# First_PCB_dip.net
KiCad netlist of a schematic drawn in Altium Designer
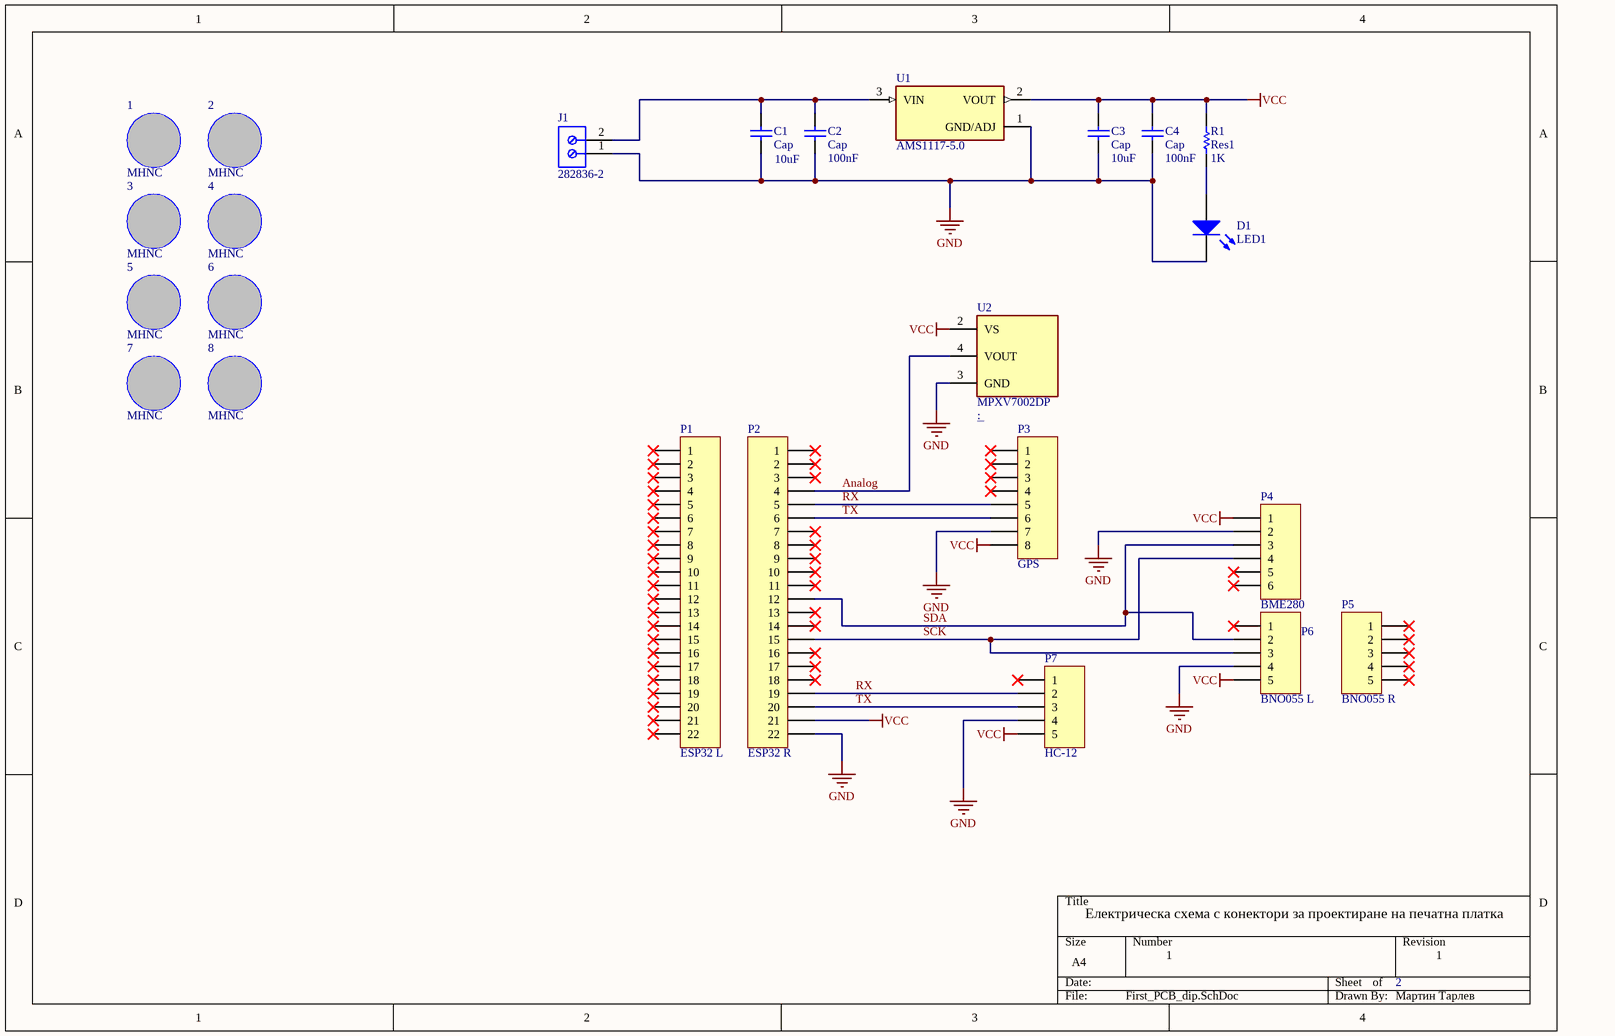
[diagram p0: First_PCB_dip.SchDoc]

(export (version "E")
  (design (tool "Eeschema 10.0.6"))
  (components
    (comp (ref "1") (value "MHNC") (footprint "MHNC") (libsource (lib "First_PCB_dip") (part "MHNC")))
    (comp (ref "2") (value "MHNC") (footprint "MHNC") (libsource (lib "First_PCB_dip") (part "MHNC")))
    (comp (ref "3") (value "MHNC") (footprint "MHNC") (libsource (lib "First_PCB_dip") (part "MHNC")))
    (comp (ref "4") (value "MHNC") (footprint "MHNC") (libsource (lib "First_PCB_dip") (part "MHNC")))
    (comp (ref "5") (value "MHNC") (footprint "MHNC") (libsource (lib "First_PCB_dip") (part "MHNC")))
    (comp (ref "6") (value "MHNC") (footprint "MHNC") (libsource (lib "First_PCB_dip") (part "MHNC")))
    (comp (ref "7") (value "MHNC") (footprint "MHNC") (libsource (lib "First_PCB_dip") (part "MHNC")))
    (comp (ref "8") (value "MHNC") (footprint "MHNC") (libsource (lib "First_PCB_dip") (part "MHNC")))
    (comp (ref "C1")
      (value "Cap")
      (footprint "CAP2")
      (description "Capacitor")
      (fields (field (name "ALTIUM_VALUE") "10uF") (field (name "PUBLISHER") "Altium Limited"))
      (libsource (lib "Miscellaneous Devices") (part "Cap"))
    )
    (comp (ref "C2")
      (value "Cap")
      (footprint "CON")
      (description "Capacitor")
      (fields (field (name "ALTIUM_VALUE") "100nF") (field (name "PUBLISHER") "Altium Limited"))
      (libsource (lib "Miscellaneous Devices") (part "Cap"))
    )
    (comp (ref "C3")
      (value "Cap")
      (footprint "CAP2")
      (description "Capacitor")
      (fields (field (name "ALTIUM_VALUE") "10uF") (field (name "PUBLISHER") "Altium Limited"))
      (libsource (lib "Miscellaneous Devices") (part "Cap"))
    )
    (comp (ref "C4")
      (value "Cap")
      (footprint "CON")
      (description "Capacitor")
      (fields (field (name "ALTIUM_VALUE") "100nF") (field (name "PUBLISHER") "Altium Limited"))
      (libsource (lib "Miscellaneous Devices") (part "Cap"))
    )
    (comp (ref "D1")
      (value "LED1")
      (footprint "LED-1")
      (description "Typical RED GaAs LED")
      (fields (field (name "PUBLISHER") "Altium Limited"))
      (libsource (lib "Miscellaneous Devices") (part "LED1"))
    )
    (comp (ref "J1")
      (value "282836-2")
      (footprint "TECO-282836-2_V")
      (description "Female Header, Pitch 5 mm, 1 x 2 Position, Height 10 mm, Tail Length 3.5 mm, Rohs, Bulk")
      (fields (field (name "VOLTAGE") "300V") (field (name "MANUFACTURER") "TE Connectivity"))
      (libsource (lib "Altium Content Vault") (part "CN-1P-F-TB2"))
    )
    (comp (ref "P1")
      (value "ESP32 L")
      (footprint "HDR1X22")
      (description "Header, 22-Pin")
      (fields (field (name "PUBLISHER") "p"))
      (libsource (lib "") (part "Header 22_1"))
    )
    (comp (ref "P2")
      (value "ESP32 R")
      (footprint "HDR1X22")
      (description "Header, 22-Pin")
      (fields (field (name "PUBLISHER") "Altium Limited"))
      (libsource (lib "Miscellaneous Connectors") (part "Header 22"))
    )
    (comp (ref "P3")
      (value "GPS")
      (footprint "HDR1X8")
      (description "Header, 8-Pin")
      (fields (field (name "PUBLISHER") "Altium Limited"))
      (libsource (lib "Miscellaneous Connectors") (part "Header 8"))
    )
    (comp (ref "P4")
      (value "BME280")
      (footprint "HDR1X6")
      (description "Header, 6-Pin")
      (fields (field (name "PUBLISHER") "Altium Limited"))
      (libsource (lib "Miscellaneous Connectors") (part "Header 6"))
    )
    (comp (ref "P5")
      (value "BNO055 R")
      (footprint "HDR1X5")
      (description "Header, 5-Pin")
      (fields (field (name "PUBLISHER") "Altium Limited"))
      (libsource (lib "") (part "Header 5_1"))
    )
    (comp (ref "P6")
      (value "BNO055 L")
      (footprint "HDR1X5")
      (description "Header, 5-Pin")
      (fields (field (name "PUBLISHER") "Altium Limited"))
      (libsource (lib "Miscellaneous Connectors") (part "Header 5"))
    )
    (comp (ref "P7")
      (value "HC-12")
      (footprint "HDR1X5")
      (description "Header, 5-Pin")
      (fields (field (name "PUBLISHER") "Altium Limited"))
      (libsource (lib "Miscellaneous Connectors") (part "Header 5"))
    )
    (comp (ref "R1")
      (value "Res1")
      (footprint "AXIAL-0.3")
      (description "Resistor")
      (fields (field (name "ALTIUM_VALUE") "1K") (field (name "PUBLISHER") "Altium Limited"))
      (libsource (lib "Miscellaneous Devices") (part "Res1"))
    )
    (comp (ref "U1")
      (value "AMS1117-5.0")
      (footprint "SOT229P700X180-4N")
      (description "1A LOW DROPOUT VOLTAGE REGULATOR")
      (fields (field (name "MF") "ams"))
      (libsource (lib "AMS1117-5.0") (part "AMS1117-5.0"))
    )
    (comp (ref "U2")
      (value "MPXV7002DP")
      (footprint "XDCR_MPXV7002DP")
      (fields (field (name "MF") "NXP USA"))
      (libsource (lib "MPXV7002DP") (part "MPXV7002DP"))
    )
  )
  (nets
    (net (code "1") (name "/Analog") (class "Default")
      (node (ref "P2") (pin "4") (pinfunction "4_4") (pintype "passive"))
      (node (ref "U2") (pin "4") (pinfunction "VOUT_4") (pintype "passive"))
    )
    (net (code "2") (name "/RX") (class "Default")
      (node (ref "P2") (pin "19") (pinfunction "19_19") (pintype "passive"))
      (node (ref "P2") (pin "5") (pinfunction "5_5") (pintype "passive"))
      (node (ref "P3") (pin "5") (pinfunction "5_5") (pintype "passive"))
      (node (ref "P7") (pin "2") (pinfunction "2_2") (pintype "passive"))
    )
    (net (code "3") (name "/SCK") (class "Default")
      (node (ref "P2") (pin "15") (pinfunction "15_15") (pintype "passive"))
      (node (ref "P4") (pin "4") (pinfunction "4_4") (pintype "passive"))
      (node (ref "P6") (pin "3") (pinfunction "3_3") (pintype "passive"))
    )
    (net (code "4") (name "/SDA") (class "Default")
      (node (ref "P2") (pin "12") (pinfunction "12_12") (pintype "passive"))
      (node (ref "P4") (pin "3") (pinfunction "3_3") (pintype "passive"))
      (node (ref "P6") (pin "2") (pinfunction "2_2") (pintype "passive"))
    )
    (net (code "5") (name "/TX") (class "Default")
      (node (ref "P2") (pin "20") (pinfunction "20_20") (pintype "passive"))
      (node (ref "P2") (pin "6") (pinfunction "6_6") (pintype "passive"))
      (node (ref "P3") (pin "6") (pinfunction "6_6") (pintype "passive"))
      (node (ref "P7") (pin "3") (pinfunction "3_3") (pintype "passive"))
    )
    (net (code "6") (name "GND") (class "Default")
      (node (ref "C1") (pin "1") (pinfunction "1_1") (pintype "passive"))
      (node (ref "C2") (pin "1") (pinfunction "1_1") (pintype "passive"))
      (node (ref "C3") (pin "1") (pinfunction "1_1") (pintype "passive"))
      (node (ref "C4") (pin "1") (pinfunction "1_1") (pintype "passive"))
      (node (ref "D1") (pin "2") (pinfunction "K_2") (pintype "passive"))
      (node (ref "J1") (pin "1") (pinfunction "1_1") (pintype "passive"))
      (node (ref "P2") (pin "22") (pinfunction "22_22") (pintype "passive"))
      (node (ref "P3") (pin "7") (pinfunction "7_7") (pintype "passive"))
      (node (ref "P4") (pin "2") (pinfunction "2_2") (pintype "passive"))
      (node (ref "P6") (pin "4") (pinfunction "4_4") (pintype "passive"))
      (node (ref "P7") (pin "4") (pinfunction "4_4") (pintype "passive"))
      (node (ref "U1") (pin "1") (pinfunction "GND/ADJ_1") (pintype "power_in"))
      (node (ref "U2") (pin "3") (pinfunction "GND_3") (pintype "power_in"))
    )
    (net (code "7") (name "Net-(D1-A)") (class "Default")
      (node (ref "D1") (pin "1") (pinfunction "A_1") (pintype "passive"))
      (node (ref "R1") (pin "1") (pinfunction "1_1") (pintype "passive"))
    )
    (net (code "8") (name "Net-(U1-VIN)") (class "Default")
      (node (ref "C1") (pin "2") (pinfunction "2_2") (pintype "passive"))
      (node (ref "C2") (pin "2") (pinfunction "2_2") (pintype "passive"))
      (node (ref "J1") (pin "2") (pinfunction "2_2") (pintype "passive"))
      (node (ref "U1") (pin "3") (pinfunction "VIN_3") (pintype "input"))
    )
    (net (code "9") (name "VCC") (class "Default")
      (node (ref "C3") (pin "2") (pinfunction "2_2") (pintype "passive"))
      (node (ref "C4") (pin "2") (pinfunction "2_2") (pintype "passive"))
      (node (ref "P2") (pin "21") (pinfunction "21_21") (pintype "passive"))
      (node (ref "P3") (pin "8") (pinfunction "8_8") (pintype "passive"))
      (node (ref "P4") (pin "1") (pinfunction "1_1") (pintype "passive"))
      (node (ref "P6") (pin "5") (pinfunction "5_5") (pintype "passive"))
      (node (ref "P7") (pin "5") (pinfunction "5_5") (pintype "passive"))
      (node (ref "R1") (pin "2") (pinfunction "2_2") (pintype "passive"))
      (node (ref "U1") (pin "2") (pinfunction "VOUT_2") (pintype "output"))
      (node (ref "U2") (pin "2") (pinfunction "VS_2") (pintype "passive"))
    )
    (net (code "10") (name "unconnected-(P1-Pad1)") (class "Default")
      (node (ref "P1") (pin "1") (pinfunction "1_1") (pintype "passive+no_connect"))
    )
    (net (code "11") (name "unconnected-(P1-Pad2)") (class "Default")
      (node (ref "P1") (pin "2") (pinfunction "2_2") (pintype "passive+no_connect"))
    )
    (net (code "12") (name "unconnected-(P1-Pad3)") (class "Default")
      (node (ref "P1") (pin "3") (pinfunction "3_3") (pintype "passive+no_connect"))
    )
    (net (code "13") (name "unconnected-(P1-Pad4)") (class "Default")
      (node (ref "P1") (pin "4") (pinfunction "4_4") (pintype "passive+no_connect"))
    )
    (net (code "14") (name "unconnected-(P1-Pad5)") (class "Default")
      (node (ref "P1") (pin "5") (pinfunction "5_5") (pintype "passive+no_connect"))
    )
    (net (code "15") (name "unconnected-(P1-Pad6)") (class "Default")
      (node (ref "P1") (pin "6") (pinfunction "6_6") (pintype "passive+no_connect"))
    )
    (net (code "16") (name "unconnected-(P1-Pad7)") (class "Default")
      (node (ref "P1") (pin "7") (pinfunction "7_7") (pintype "passive+no_connect"))
    )
    (net (code "17") (name "unconnected-(P1-Pad8)") (class "Default")
      (node (ref "P1") (pin "8") (pinfunction "8_8") (pintype "passive+no_connect"))
    )
    (net (code "18") (name "unconnected-(P1-Pad9)") (class "Default")
      (node (ref "P1") (pin "9") (pinfunction "9_9") (pintype "passive+no_connect"))
    )
    (net (code "19") (name "unconnected-(P1-Pad10)") (class "Default")
      (node (ref "P1") (pin "10") (pinfunction "10_10") (pintype "passive+no_connect"))
    )
    (net (code "20") (name "unconnected-(P1-Pad11)") (class "Default")
      (node (ref "P1") (pin "11") (pinfunction "11_11") (pintype "passive+no_connect"))
    )
    (net (code "21") (name "unconnected-(P1-Pad12)") (class "Default")
      (node (ref "P1") (pin "12") (pinfunction "12_12") (pintype "passive+no_connect"))
    )
    (net (code "22") (name "unconnected-(P1-Pad13)") (class "Default")
      (node (ref "P1") (pin "13") (pinfunction "13_13") (pintype "passive+no_connect"))
    )
    (net (code "23") (name "unconnected-(P1-Pad14)") (class "Default")
      (node (ref "P1") (pin "14") (pinfunction "14_14") (pintype "passive+no_connect"))
    )
    (net (code "24") (name "unconnected-(P1-Pad15)") (class "Default")
      (node (ref "P1") (pin "15") (pinfunction "15_15") (pintype "passive+no_connect"))
    )
    (net (code "25") (name "unconnected-(P1-Pad16)") (class "Default")
      (node (ref "P1") (pin "16") (pinfunction "16_16") (pintype "passive+no_connect"))
    )
    (net (code "26") (name "unconnected-(P1-Pad17)") (class "Default")
      (node (ref "P1") (pin "17") (pinfunction "17_17") (pintype "passive+no_connect"))
    )
    (net (code "27") (name "unconnected-(P1-Pad18)") (class "Default")
      (node (ref "P1") (pin "18") (pinfunction "18_18") (pintype "passive+no_connect"))
    )
    (net (code "28") (name "unconnected-(P1-Pad19)") (class "Default")
      (node (ref "P1") (pin "19") (pinfunction "19_19") (pintype "passive+no_connect"))
    )
    (net (code "29") (name "unconnected-(P1-Pad20)") (class "Default")
      (node (ref "P1") (pin "20") (pinfunction "20_20") (pintype "passive+no_connect"))
    )
    (net (code "30") (name "unconnected-(P1-Pad21)") (class "Default")
      (node (ref "P1") (pin "21") (pinfunction "21_21") (pintype "passive+no_connect"))
    )
    (net (code "31") (name "unconnected-(P1-Pad22)") (class "Default")
      (node (ref "P1") (pin "22") (pinfunction "22_22") (pintype "passive+no_connect"))
    )
    (net (code "32") (name "unconnected-(P2-Pad1)") (class "Default")
      (node (ref "P2") (pin "1") (pinfunction "1_1") (pintype "passive+no_connect"))
    )
    (net (code "33") (name "unconnected-(P2-Pad2)") (class "Default")
      (node (ref "P2") (pin "2") (pinfunction "2_2") (pintype "passive+no_connect"))
    )
    (net (code "34") (name "unconnected-(P2-Pad3)") (class "Default")
      (node (ref "P2") (pin "3") (pinfunction "3_3") (pintype "passive+no_connect"))
    )
    (net (code "35") (name "unconnected-(P2-Pad7)") (class "Default")
      (node (ref "P2") (pin "7") (pinfunction "7_7") (pintype "passive+no_connect"))
    )
    (net (code "36") (name "unconnected-(P2-Pad8)") (class "Default")
      (node (ref "P2") (pin "8") (pinfunction "8_8") (pintype "passive+no_connect"))
    )
    (net (code "37") (name "unconnected-(P2-Pad9)") (class "Default")
      (node (ref "P2") (pin "9") (pinfunction "9_9") (pintype "passive+no_connect"))
    )
    (net (code "38") (name "unconnected-(P2-Pad10)") (class "Default")
      (node (ref "P2") (pin "10") (pinfunction "10_10") (pintype "passive+no_connect"))
    )
    (net (code "39") (name "unconnected-(P2-Pad11)") (class "Default")
      (node (ref "P2") (pin "11") (pinfunction "11_11") (pintype "passive+no_connect"))
    )
    (net (code "40") (name "unconnected-(P2-Pad13)") (class "Default")
      (node (ref "P2") (pin "13") (pinfunction "13_13") (pintype "passive+no_connect"))
    )
    (net (code "41") (name "unconnected-(P2-Pad14)") (class "Default")
      (node (ref "P2") (pin "14") (pinfunction "14_14") (pintype "passive+no_connect"))
    )
    (net (code "42") (name "unconnected-(P2-Pad16)") (class "Default")
      (node (ref "P2") (pin "16") (pinfunction "16_16") (pintype "passive+no_connect"))
    )
    (net (code "43") (name "unconnected-(P2-Pad17)") (class "Default")
      (node (ref "P2") (pin "17") (pinfunction "17_17") (pintype "passive+no_connect"))
    )
    (net (code "44") (name "unconnected-(P2-Pad18)") (class "Default")
      (node (ref "P2") (pin "18") (pinfunction "18_18") (pintype "passive+no_connect"))
    )
    (net (code "45") (name "unconnected-(P3-Pad1)") (class "Default")
      (node (ref "P3") (pin "1") (pinfunction "1_1") (pintype "passive+no_connect"))
    )
    (net (code "46") (name "unconnected-(P3-Pad2)") (class "Default")
      (node (ref "P3") (pin "2") (pinfunction "2_2") (pintype "passive+no_connect"))
    )
    (net (code "47") (name "unconnected-(P3-Pad3)") (class "Default")
      (node (ref "P3") (pin "3") (pinfunction "3_3") (pintype "passive+no_connect"))
    )
    (net (code "48") (name "unconnected-(P3-Pad4)") (class "Default")
      (node (ref "P3") (pin "4") (pinfunction "4_4") (pintype "passive+no_connect"))
    )
    (net (code "49") (name "unconnected-(P4-Pad5)") (class "Default")
      (node (ref "P4") (pin "5") (pinfunction "5_5") (pintype "passive+no_connect"))
    )
    (net (code "50") (name "unconnected-(P4-Pad6)") (class "Default")
      (node (ref "P4") (pin "6") (pinfunction "6_6") (pintype "passive+no_connect"))
    )
    (net (code "51") (name "unconnected-(P5-Pad1)") (class "Default")
      (node (ref "P5") (pin "1") (pinfunction "1_1") (pintype "passive+no_connect"))
    )
    (net (code "52") (name "unconnected-(P5-Pad2)") (class "Default")
      (node (ref "P5") (pin "2") (pinfunction "2_2") (pintype "passive+no_connect"))
    )
    (net (code "53") (name "unconnected-(P5-Pad3)") (class "Default")
      (node (ref "P5") (pin "3") (pinfunction "3_3") (pintype "passive+no_connect"))
    )
    (net (code "54") (name "unconnected-(P5-Pad4)") (class "Default")
      (node (ref "P5") (pin "4") (pinfunction "4_4") (pintype "passive+no_connect"))
    )
    (net (code "55") (name "unconnected-(P5-Pad5)") (class "Default")
      (node (ref "P5") (pin "5") (pinfunction "5_5") (pintype "passive+no_connect"))
    )
    (net (code "56") (name "unconnected-(P6-Pad1)") (class "Default")
      (node (ref "P6") (pin "1") (pinfunction "1_1") (pintype "passive+no_connect"))
    )
    (net (code "57") (name "unconnected-(P7-Pad1)") (class "Default")
      (node (ref "P7") (pin "1") (pinfunction "1_1") (pintype "passive+no_connect"))
    )
  )
)
